# FEU_Last.net
KiCad netlist of a schematic drawn in EAGLE
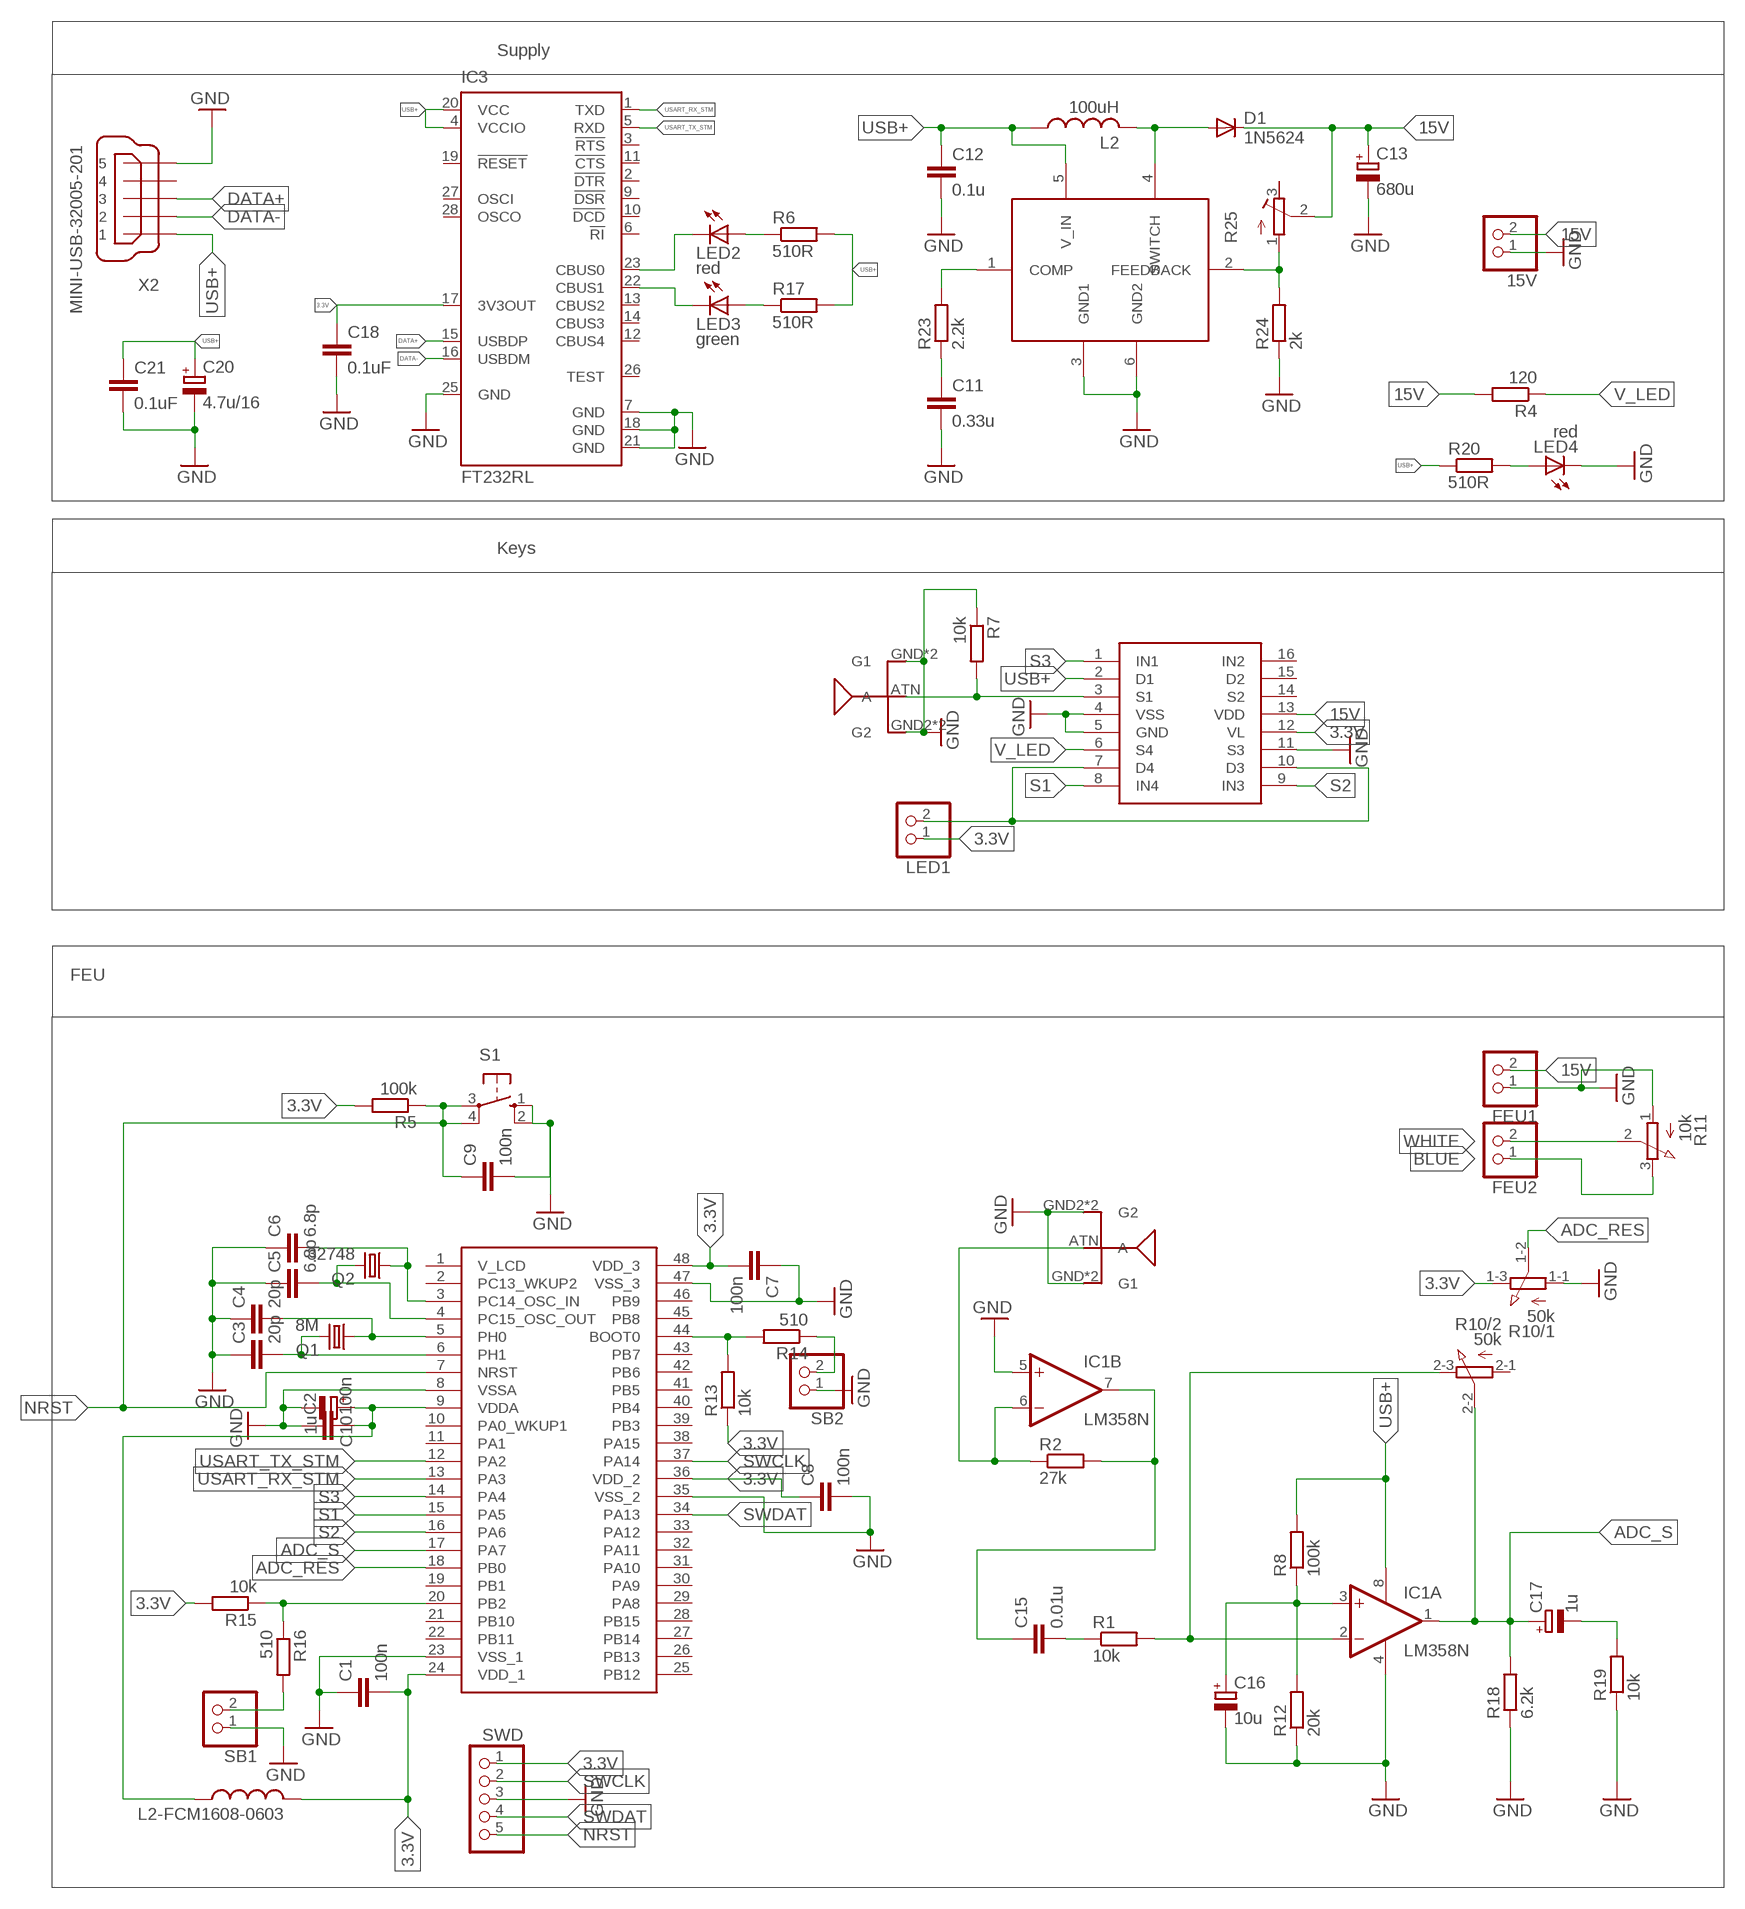
[diagram p0: schematic, sheet 1]

(export (version "E")
  (design (tool "Eeschema 10.0.6"))
  (components
    (comp (ref "15V")
      (value "PINHD-1X2")
      (footprint "eagle-import:1X02")
      (libsource (lib "eagle-import") (part "PINHD-1X2"))
    )
    (comp (ref "C1")
      (value "100n")
      (footprint "eagle-import:C0805")
      (libsource (lib "eagle-import") (part "C-EUC0805"))
    )
    (comp (ref "C2")
      (value "100n")
      (footprint "eagle-import:C0805")
      (libsource (lib "eagle-import") (part "C-EUC0805"))
    )
    (comp (ref "C3")
      (value "20p")
      (footprint "eagle-import:C0805")
      (libsource (lib "eagle-import") (part "C-EUC0805"))
    )
    (comp (ref "C4")
      (value "20p")
      (footprint "eagle-import:C0805")
      (libsource (lib "eagle-import") (part "C-EUC0805"))
    )
    (comp (ref "C5")
      (value "6.8p")
      (footprint "eagle-import:C0805")
      (libsource (lib "eagle-import") (part "C-EUC0805"))
    )
    (comp (ref "C6")
      (value "6.8p")
      (footprint "eagle-import:C0805")
      (libsource (lib "eagle-import") (part "C-EUC0805"))
    )
    (comp (ref "C7")
      (value "100n")
      (footprint "eagle-import:C0805")
      (libsource (lib "eagle-import") (part "C-EUC0805"))
    )
    (comp (ref "C8")
      (value "100n")
      (footprint "eagle-import:C0805")
      (libsource (lib "eagle-import") (part "C-EUC0805"))
    )
    (comp (ref "C9")
      (value "100n")
      (footprint "eagle-import:C0805")
      (libsource (lib "eagle-import") (part "C-EUC0805"))
    )
    (comp (ref "C10")
      (value "1u")
      (footprint "eagle-import:A_3216-18W")
      (libsource (lib "eagle-import") (part "CPOL-EUA/3216-18W"))
    )
    (comp (ref "C11")
      (value "0.33u")
      (footprint "eagle-import:C0805")
      (libsource (lib "eagle-import") (part "C-EUC0805"))
    )
    (comp (ref "C12")
      (value "0.1u")
      (footprint "eagle-import:C0805")
      (libsource (lib "eagle-import") (part "C-EUC0805"))
    )
    (comp (ref "C13")
      (value "680u")
      (footprint "eagle-import:E5-5")
      (libsource (lib "eagle-import") (part "CPOL-EUE5-5"))
    )
    (comp (ref "C15")
      (value "0.01u")
      (footprint "eagle-import:C0805")
      (libsource (lib "eagle-import") (part "C-EUC0805"))
    )
    (comp (ref "C16")
      (value "10u")
      (footprint "eagle-import:E3,5-8")
      (libsource (lib "eagle-import") (part "CPOL-EUE3.5-8"))
    )
    (comp (ref "C17")
      (value "1u")
      (footprint "eagle-import:E3,5-8")
      (libsource (lib "eagle-import") (part "CPOL-EUE3.5-8"))
    )
    (comp (ref "C18")
      (value "0.1uF")
      (footprint "eagle-import:C0805")
      (libsource (lib "eagle-import") (part "C-EUC0805"))
    )
    (comp (ref "C20")
      (value "4.7u/16")
      (footprint "eagle-import:E2-5")
      (libsource (lib "eagle-import") (part "CPOL-EUE2-5"))
    )
    (comp (ref "C21")
      (value "0.1uF")
      (footprint "eagle-import:C0805")
      (libsource (lib "eagle-import") (part "C-EUC0805"))
    )
    (comp (ref "D1")
      (value "1N5624")
      (footprint "eagle-import:DO201-15")
      (libsource (lib "eagle-import") (part "1N5624"))
    )
    (comp (ref "FEU1")
      (value "PINHD-1X2")
      (footprint "eagle-import:1X02")
      (libsource (lib "eagle-import") (part "PINHD-1X2"))
    )
    (comp (ref "FEU2")
      (value "PINHD-1X2")
      (footprint "eagle-import:1X02")
      (libsource (lib "eagle-import") (part "PINHD-1X2"))
    )
    (comp (ref "IC1")
      (value "LM358N")
      (footprint "eagle-import:DIL08")
      (libsource (lib "eagle-import") (part "LM358N"))
    )
    (comp (ref "IC3")
      (value "FT232RL")
      (footprint "eagle-import:SSOP28")
      (libsource (lib "eagle-import") (part "FT232RL"))
    )
    (comp (ref "L2")
      (value "100uH")
      (footprint "eagle-import:0207_5V")
      (libsource (lib "eagle-import") (part "L-US0207/5V"))
    )
    (comp (ref "L2-FCM1608-0603")
      (value "L-USL3216C")
      (footprint "eagle-import:L3216C")
      (libsource (lib "eagle-import") (part "L-USL3216C"))
    )
    (comp (ref "LED1")
      (value "PINHD-1X2")
      (footprint "eagle-import:1X02")
      (libsource (lib "eagle-import") (part "PINHD-1X2"))
    )
    (comp (ref "LED2")
      (value "red")
      (footprint "eagle-import:CHIPLED_1206")
      (libsource (lib "eagle-import") (part "LEDCHIPLED_1206"))
    )
    (comp (ref "LED3")
      (value "green")
      (footprint "eagle-import:CHIPLED_1206")
      (libsource (lib "eagle-import") (part "LEDCHIPLED_1206"))
    )
    (comp (ref "LED4")
      (value "red")
      (footprint "eagle-import:CHIPLED_1206")
      (libsource (lib "eagle-import") (part "LEDCHIPLED_1206"))
    )
    (comp (ref "Q1")
      (value "8M")
      (footprint "eagle-import:HC49_S")
      (fields (field (name "OC_FARNELL") "1667008"))
      (libsource (lib "eagle-import") (part "CRYSTALHC49S"))
    )
    (comp (ref "Q2")
      (value "32748")
      (footprint "eagle-import:TC26H")
      (libsource (lib "eagle-import") (part "CRYSTALTC26H"))
    )
    (comp (ref "R1")
      (value "10k")
      (footprint "eagle-import:R0805")
      (libsource (lib "eagle-import") (part "R-EU_R0805"))
    )
    (comp (ref "R2")
      (value "27k")
      (footprint "eagle-import:R0805")
      (libsource (lib "eagle-import") (part "R-EU_R0805"))
    )
    (comp (ref "R4")
      (value "120")
      (footprint "eagle-import:R0805")
      (libsource (lib "eagle-import") (part "R-EU_R0805"))
    )
    (comp (ref "R5")
      (value "100k")
      (footprint "eagle-import:R0805")
      (libsource (lib "eagle-import") (part "R-EU_R0805"))
    )
    (comp (ref "R6")
      (value "510R")
      (footprint "eagle-import:R0805W")
      (libsource (lib "eagle-import") (part "R-EU_R0805W"))
    )
    (comp (ref "R7")
      (value "10k")
      (footprint "eagle-import:R0805")
      (libsource (lib "eagle-import") (part "R-EU_R0805"))
    )
    (comp (ref "R8")
      (value "100k")
      (footprint "eagle-import:R0805")
      (libsource (lib "eagle-import") (part "R-EU_R0805"))
    )
    (comp (ref "R10")
      (value "50k")
      (footprint "eagle-import:3RP_1610G")
      (libsource (lib "eagle-import") (part "3RP/1610G"))
    )
    (comp (ref "R11")
      (value "10k")
      (footprint "eagle-import:3RP_1610N")
      (libsource (lib "eagle-import") (part "3RP/1610N"))
    )
    (comp (ref "R12")
      (value "20k")
      (footprint "eagle-import:R0805")
      (libsource (lib "eagle-import") (part "R-EU_R0805"))
    )
    (comp (ref "R13")
      (value "10k")
      (footprint "eagle-import:R0805")
      (libsource (lib "eagle-import") (part "R-EU_R0805"))
    )
    (comp (ref "R14")
      (value "510")
      (footprint "eagle-import:R0805")
      (libsource (lib "eagle-import") (part "R-EU_R0805"))
    )
    (comp (ref "R15")
      (value "10k")
      (footprint "eagle-import:M0805")
      (libsource (lib "eagle-import") (part "R-EU_M0805"))
    )
    (comp (ref "R16")
      (value "510")
      (footprint "eagle-import:R0805")
      (libsource (lib "eagle-import") (part "R-EU_R0805"))
    )
    (comp (ref "R17")
      (value "510R")
      (footprint "eagle-import:R0805W")
      (libsource (lib "eagle-import") (part "R-EU_R0805W"))
    )
    (comp (ref "R18")
      (value "6.2k")
      (footprint "eagle-import:R0805")
      (libsource (lib "eagle-import") (part "R-EU_R0805"))
    )
    (comp (ref "R19")
      (value "10k")
      (footprint "eagle-import:R0805")
      (libsource (lib "eagle-import") (part "R-EU_R0805"))
    )
    (comp (ref "R20")
      (value "510R")
      (footprint "eagle-import:R0805W")
      (libsource (lib "eagle-import") (part "R-EU_R0805W"))
    )
    (comp (ref "R23")
      (value "2.2k")
      (footprint "eagle-import:R0805")
      (libsource (lib "eagle-import") (part "R-EU_R0805"))
    )
    (comp (ref "R24")
      (value "2k")
      (footprint "eagle-import:R0805")
      (libsource (lib "eagle-import") (part "R-EU_R0805"))
    )
    (comp (ref "R25")
      (value "R-TRIMM3339P")
      (footprint "eagle-import:RTRIM3339P")
      (libsource (lib "eagle-import") (part "R-TRIMM3339P"))
    )
    (comp (ref "S1")
      (value "10-XX")
      (footprint "eagle-import:B3F-10XX")
      (fields (field (name "MPN") "B3F-1000"))
      (libsource (lib "eagle-import") (part "10-XX"))
    )
    (comp (ref "SB1")
      (value "PINHD-1X2")
      (footprint "eagle-import:1X02")
      (libsource (lib "eagle-import") (part "PINHD-1X2"))
    )
    (comp (ref "SB2")
      (value "PINHD-1X2")
      (footprint "eagle-import:1X02")
      (libsource (lib "eagle-import") (part "PINHD-1X2"))
    )
    (comp (ref "SWD")
      (value "PINHD-1X5")
      (footprint "eagle-import:1X05")
      (libsource (lib "eagle-import") (part "PINHD-1X5"))
    )
    (comp (ref "U$1")
      (value "STM32L152C6")
      (footprint "eagle-import:LQFP48")
      (libsource (lib "eagle-import") (part "STM32L152C6"))
    )
    (comp (ref "U$2")
      (value "GSM_ANT")
      (footprint "eagle-import:GSM")
      (libsource (lib "eagle-import") (part "GSM_ANT"))
    )
    (comp (ref "U$3")
      (value "GSM_ANT")
      (footprint "eagle-import:GSM")
      (libsource (lib "eagle-import") (part "GSM_ANT"))
    )
    (comp (ref "U$4")
      (value "LM2577")
      (footprint "eagle-import:TO263-5")
      (libsource (lib "eagle-import") (part "LM2577"))
    )
    (comp (ref "U$5")
      (value "ADG433BN")
      (footprint "eagle-import:DIL16")
      (libsource (lib "eagle-import") (part "ADG433BN"))
    )
    (comp (ref "X2")
      (value "MINI-USB-32005-201")
      (footprint "eagle-import:32005-201")
      (libsource (lib "eagle-import") (part "MINI-USB-32005-201"))
    )
  )
  (nets
    (net (code "1") (name "3.3V") (class "Default")
      (node (ref "C1") (pin "2") (pinfunction "2_2") (pintype "passive"))
      (node (ref "C18") (pin "1") (pinfunction "1_1") (pintype "passive"))
      (node (ref "C7") (pin "2") (pinfunction "2_2") (pintype "passive"))
      (node (ref "C8") (pin "1") (pinfunction "1_1") (pintype "passive"))
      (node (ref "IC3") (pin "17") (pinfunction "3V3OUT_17") (pintype "output"))
      (node (ref "L2-FCM1608-0603") (pin "2") (pinfunction "2_2") (pintype "passive"))
      (node (ref "LED1") (pin "1") (pinfunction "1_1") (pintype "passive"))
      (node (ref "R10") (pin "1-3") (pinfunction "E_1-3") (pintype "passive"))
      (node (ref "R13") (pin "1") (pinfunction "1_1") (pintype "passive"))
      (node (ref "R15") (pin "2") (pinfunction "2_2") (pintype "passive"))
      (node (ref "R5") (pin "2") (pinfunction "2_2") (pintype "passive"))
      (node (ref "SWD") (pin "1") (pinfunction "1_1") (pintype "passive"))
      (node (ref "U$1") (pin "24") (pinfunction "VDD_1_24") (pintype "bidirectional"))
      (node (ref "U$1") (pin "36") (pinfunction "VDD_2_36") (pintype "bidirectional"))
      (node (ref "U$1") (pin "48") (pinfunction "VDD_3_48") (pintype "bidirectional"))
      (node (ref "U$5") (pin "12") (pinfunction "VL_12") (pintype "bidirectional"))
    )
    (net (code "2") (name "15V") (class "Default")
      (node (ref "15V") (pin "2") (pinfunction "2_2") (pintype "passive"))
      (node (ref "C13") (pin "+") (pinfunction "+_+") (pintype "passive"))
      (node (ref "D1") (pin "C") (pinfunction "C_C") (pintype "passive"))
      (node (ref "FEU1") (pin "2") (pinfunction "2_2") (pintype "passive"))
      (node (ref "R25") (pin "2") (pinfunction "S_2") (pintype "passive"))
      (node (ref "R4") (pin "2") (pinfunction "2_2") (pintype "passive"))
      (node (ref "U$5") (pin "13") (pinfunction "VDD_13") (pintype "bidirectional"))
    )
    (net (code "3") (name "ADC_RES") (class "Default")
      (node (ref "R10") (pin "1-2") (pinfunction "S_1-2") (pintype "passive"))
      (node (ref "U$1") (pin "18") (pinfunction "PB0_18") (pintype "bidirectional"))
    )
    (net (code "4") (name "ADC_S") (class "Default")
      (node (ref "C17") (pin "+") (pinfunction "+_+") (pintype "passive"))
      (node (ref "IC1") (pin "1") (pinfunction "OUT_1") (pintype "output"))
      (node (ref "R10") (pin "2-2") (pinfunction "S_2-2") (pintype "passive"))
      (node (ref "R18") (pin "2") (pinfunction "2_2") (pintype "passive"))
      (node (ref "U$1") (pin "17") (pinfunction "PA7_17") (pintype "bidirectional"))
    )
    (net (code "5") (name "BLUE") (class "Default")
      (node (ref "FEU2") (pin "1") (pinfunction "1_1") (pintype "passive"))
      (node (ref "R11") (pin "3") (pinfunction "E_3") (pintype "passive"))
    )
    (net (code "6") (name "DATA+") (class "Default")
      (node (ref "IC3") (pin "15") (pinfunction "USBDP_15") (pintype "bidirectional"))
      (node (ref "X2") (pin "3") (pinfunction "3_3") (pintype "passive"))
    )
    (net (code "7") (name "DATA-") (class "Default")
      (node (ref "IC3") (pin "16") (pinfunction "USBDM_16") (pintype "bidirectional"))
      (node (ref "X2") (pin "2") (pinfunction "2_2") (pintype "passive"))
    )
    (net (code "8") (name "GND") (class "Default")
      (node (ref "15V") (pin "1") (pinfunction "1_1") (pintype "passive"))
      (node (ref "C1") (pin "1") (pinfunction "1_1") (pintype "passive"))
      (node (ref "C10") (pin "-") (pinfunction "-_-") (pintype "passive"))
      (node (ref "C11") (pin "2") (pinfunction "2_2") (pintype "passive"))
      (node (ref "C12") (pin "2") (pinfunction "2_2") (pintype "passive"))
      (node (ref "C13") (pin "-") (pinfunction "-_-") (pintype "passive"))
      (node (ref "C16") (pin "-") (pinfunction "-_-") (pintype "passive"))
      (node (ref "C18") (pin "2") (pinfunction "2_2") (pintype "passive"))
      (node (ref "C2") (pin "1") (pinfunction "1_1") (pintype "passive"))
      (node (ref "C20") (pin "-") (pinfunction "-_-") (pintype "passive"))
      (node (ref "C21") (pin "2") (pinfunction "2_2") (pintype "passive"))
      (node (ref "C3") (pin "1") (pinfunction "1_1") (pintype "passive"))
      (node (ref "C4") (pin "1") (pinfunction "1_1") (pintype "passive"))
      (node (ref "C5") (pin "1") (pinfunction "1_1") (pintype "passive"))
      (node (ref "C6") (pin "1") (pinfunction "1_1") (pintype "passive"))
      (node (ref "C7") (pin "1") (pinfunction "1_1") (pintype "passive"))
      (node (ref "C8") (pin "2") (pinfunction "2_2") (pintype "passive"))
      (node (ref "C9") (pin "2") (pinfunction "2_2") (pintype "passive"))
      (node (ref "FEU1") (pin "1") (pinfunction "1_1") (pintype "passive"))
      (node (ref "IC1") (pin "4") (pinfunction "V-_4") (pintype "power_in"))
      (node (ref "IC1") (pin "5") (pinfunction "+IN_5") (pintype "input"))
      (node (ref "IC3") (pin "18") (pinfunction "GND_18") (pintype "power_in"))
      (node (ref "IC3") (pin "21") (pinfunction "GND_21") (pintype "power_in"))
      (node (ref "IC3") (pin "25") (pinfunction "GND_25") (pintype "power_in"))
      (node (ref "IC3") (pin "7") (pinfunction "GND_7") (pintype "power_in"))
      (node (ref "LED4") (pin "C") (pinfunction "C_C") (pintype "passive"))
      (node (ref "R10") (pin "1-1") (pinfunction "A_1-1") (pintype "passive"))
      (node (ref "R11") (pin "1") (pinfunction "A_1") (pintype "passive"))
      (node (ref "R12") (pin "1") (pinfunction "1_1") (pintype "passive"))
      (node (ref "R18") (pin "1") (pinfunction "1_1") (pintype "passive"))
      (node (ref "R19") (pin "1") (pinfunction "1_1") (pintype "passive"))
      (node (ref "R24") (pin "1") (pinfunction "1_1") (pintype "passive"))
      (node (ref "R7") (pin "1") (pinfunction "1_1") (pintype "passive"))
      (node (ref "S1") (pin "1") (pinfunction "S_1") (pintype "passive"))
      (node (ref "S1") (pin "2") (pinfunction "S1_2") (pintype "passive"))
      (node (ref "SB1") (pin "1") (pinfunction "1_1") (pintype "passive"))
      (node (ref "SB2") (pin "1") (pinfunction "1_1") (pintype "passive"))
      (node (ref "SWD") (pin "3") (pinfunction "3_3") (pintype "passive"))
      (node (ref "U$1") (pin "23") (pinfunction "VSS_1_23") (pintype "bidirectional"))
      (node (ref "U$1") (pin "35") (pinfunction "VSS_2_35") (pintype "bidirectional"))
      (node (ref "U$1") (pin "47") (pinfunction "VSS_3_47") (pintype "bidirectional"))
      (node (ref "U$1") (pin "8") (pinfunction "VSSA_8") (pintype "bidirectional"))
      (node (ref "U$2") (pin "GND") (pinfunction "G1_GND") (pintype "bidirectional"))
      (node (ref "U$2") (pin "GND1") (pinfunction "G1_GND1") (pintype "bidirectional"))
      (node (ref "U$2") (pin "GND2") (pinfunction "G2_GND2") (pintype "bidirectional"))
      (node (ref "U$2") (pin "GND3") (pinfunction "G2_GND3") (pintype "bidirectional"))
      (node (ref "U$3") (pin "GND") (pinfunction "G1_GND") (pintype "bidirectional"))
      (node (ref "U$3") (pin "GND1") (pinfunction "G1_GND1") (pintype "bidirectional"))
      (node (ref "U$3") (pin "GND2") (pinfunction "G2_GND2") (pintype "bidirectional"))
      (node (ref "U$3") (pin "GND3") (pinfunction "G2_GND3") (pintype "bidirectional"))
      (node (ref "U$4") (pin "3") (pinfunction "GND1_3") (pintype "bidirectional"))
      (node (ref "U$4") (pin "6") (pinfunction "GND2_6") (pintype "bidirectional"))
      (node (ref "U$5") (pin "11") (pinfunction "S3_11") (pintype "bidirectional"))
      (node (ref "U$5") (pin "4") (pinfunction "VSS_4") (pintype "bidirectional"))
      (node (ref "U$5") (pin "5") (pinfunction "GND_5") (pintype "bidirectional"))
      (node (ref "X2") (pin "5") (pinfunction "5_5") (pintype "passive"))
    )
    (net (code "9") (name "NRST") (class "Default")
      (node (ref "C9") (pin "1") (pinfunction "1_1") (pintype "passive"))
      (node (ref "R5") (pin "1") (pinfunction "1_1") (pintype "passive"))
      (node (ref "S1") (pin "3") (pinfunction "P_3") (pintype "passive"))
      (node (ref "S1") (pin "4") (pinfunction "P1_4") (pintype "passive"))
      (node (ref "SWD") (pin "5") (pinfunction "5_5") (pintype "passive"))
      (node (ref "U$1") (pin "7") (pinfunction "NRST_7") (pintype "bidirectional"))
    )
    (net (code "10") (name "Net-(C11-Pad1)") (class "Default")
      (node (ref "C11") (pin "1") (pinfunction "1_1") (pintype "passive"))
      (node (ref "R23") (pin "1") (pinfunction "1_1") (pintype "passive"))
    )
    (net (code "11") (name "Net-(C15-Pad2)") (class "Default")
      (node (ref "C15") (pin "2") (pinfunction "2_2") (pintype "passive"))
      (node (ref "R1") (pin "1") (pinfunction "1_1") (pintype "passive"))
    )
    (net (code "12") (name "Net-(C17-Pad-)") (class "Default")
      (node (ref "C17") (pin "-") (pinfunction "-_-") (pintype "passive"))
      (node (ref "R19") (pin "2") (pinfunction "2_2") (pintype "passive"))
    )
    (net (code "13") (name "Net-(IC1A-+IN)") (class "Default")
      (node (ref "C16") (pin "+") (pinfunction "+_+") (pintype "passive"))
      (node (ref "IC1") (pin "3") (pinfunction "+IN_3") (pintype "input"))
      (node (ref "R12") (pin "2") (pinfunction "2_2") (pintype "passive"))
      (node (ref "R8") (pin "1") (pinfunction "1_1") (pintype "passive"))
    )
    (net (code "14") (name "Net-(IC1A--IN)") (class "Default")
      (node (ref "IC1") (pin "2") (pinfunction "-IN_2") (pintype "input"))
      (node (ref "R1") (pin "2") (pinfunction "2_2") (pintype "passive"))
      (node (ref "R10") (pin "2-3") (pinfunction "E_2-3") (pintype "passive"))
    )
    (net (code "15") (name "Net-(IC1B--IN)") (class "Default")
      (node (ref "IC1") (pin "6") (pinfunction "-IN_6") (pintype "input"))
      (node (ref "R2") (pin "1") (pinfunction "1_1") (pintype "passive"))
      (node (ref "U$2") (pin "ATN") (pinfunction "A_ATN") (pintype "bidirectional"))
    )
    (net (code "16") (name "Net-(IC1B-OUT)") (class "Default")
      (node (ref "C15") (pin "1") (pinfunction "1_1") (pintype "passive"))
      (node (ref "IC1") (pin "7") (pinfunction "OUT_7") (pintype "output"))
      (node (ref "R2") (pin "2") (pinfunction "2_2") (pintype "passive"))
    )
    (net (code "17") (name "Net-(IC3-CBUS0)") (class "Default")
      (node (ref "IC3") (pin "23") (pinfunction "CBUS0_23") (pintype "bidirectional"))
      (node (ref "LED2") (pin "C") (pinfunction "C_C") (pintype "passive"))
    )
    (net (code "18") (name "Net-(IC3-CBUS1)") (class "Default")
      (node (ref "IC3") (pin "22") (pinfunction "CBUS1_22") (pintype "bidirectional"))
      (node (ref "LED3") (pin "C") (pinfunction "C_C") (pintype "passive"))
    )
    (net (code "19") (name "Net-(LED2-PadA)") (class "Default")
      (node (ref "LED2") (pin "A") (pinfunction "A_A") (pintype "passive"))
      (node (ref "R6") (pin "1") (pinfunction "1_1") (pintype "passive"))
    )
    (net (code "20") (name "Net-(LED3-PadA)") (class "Default")
      (node (ref "LED3") (pin "A") (pinfunction "A_A") (pintype "passive"))
      (node (ref "R17") (pin "1") (pinfunction "1_1") (pintype "passive"))
    )
    (net (code "21") (name "Net-(LED4-PadA)") (class "Default")
      (node (ref "LED4") (pin "A") (pinfunction "A_A") (pintype "passive"))
      (node (ref "R20") (pin "2") (pinfunction "2_2") (pintype "passive"))
    )
    (net (code "22") (name "Net-(R14-Pad1)") (class "Default")
      (node (ref "R14") (pin "1") (pinfunction "1_1") (pintype "passive"))
      (node (ref "SB2") (pin "2") (pinfunction "2_2") (pintype "passive"))
    )
    (net (code "23") (name "Net-(R16-Pad2)") (class "Default")
      (node (ref "R16") (pin "2") (pinfunction "2_2") (pintype "passive"))
      (node (ref "SB1") (pin "2") (pinfunction "2_2") (pintype "passive"))
    )
    (net (code "24") (name "Net-(R25-E)") (class "Default")
      (node (ref "R24") (pin "2") (pinfunction "2_2") (pintype "passive"))
      (node (ref "R25") (pin "1") (pinfunction "E_1") (pintype "passive"))
      (node (ref "U$4") (pin "2") (pinfunction "FEEDBACK_2") (pintype "bidirectional"))
    )
    (net (code "25") (name "Net-(U$1-BOOT0)") (class "Default")
      (node (ref "R13") (pin "2") (pinfunction "2_2") (pintype "passive"))
      (node (ref "R14") (pin "2") (pinfunction "2_2") (pintype "passive"))
      (node (ref "U$1") (pin "44") (pinfunction "BOOT0_44") (pintype "bidirectional"))
    )
    (net (code "26") (name "Net-(U$1-PB2)") (class "Default")
      (node (ref "R15") (pin "1") (pinfunction "1_1") (pintype "passive"))
      (node (ref "R16") (pin "1") (pinfunction "1_1") (pintype "passive"))
      (node (ref "U$1") (pin "20") (pinfunction "PB2_20") (pintype "bidirectional"))
    )
    (net (code "27") (name "Net-(U$1-PC14_OSC_IN)") (class "Default")
      (node (ref "C6") (pin "2") (pinfunction "2_2") (pintype "passive"))
      (node (ref "Q2") (pin "1") (pinfunction "1_1") (pintype "passive"))
      (node (ref "U$1") (pin "3") (pinfunction "PC14_OSC_IN_3") (pintype "bidirectional"))
    )
    (net (code "28") (name "Net-(U$1-PC15_OSC_OUT)") (class "Default")
      (node (ref "C5") (pin "2") (pinfunction "2_2") (pintype "passive"))
      (node (ref "Q2") (pin "2") (pinfunction "2_2") (pintype "passive"))
      (node (ref "U$1") (pin "4") (pinfunction "PC15_OSC_OUT_4") (pintype "bidirectional"))
    )
    (net (code "29") (name "Net-(U$1-PH0)") (class "Default")
      (node (ref "C4") (pin "2") (pinfunction "2_2") (pintype "passive"))
      (node (ref "Q1") (pin "1") (pinfunction "1_1") (pintype "passive"))
      (node (ref "U$1") (pin "5") (pinfunction "PH0_5") (pintype "bidirectional"))
    )
    (net (code "30") (name "Net-(U$1-PH1)") (class "Default")
      (node (ref "C3") (pin "2") (pinfunction "2_2") (pintype "passive"))
      (node (ref "Q1") (pin "2") (pinfunction "2_2") (pintype "passive"))
      (node (ref "U$1") (pin "6") (pinfunction "PH1_6") (pintype "bidirectional"))
    )
    (net (code "31") (name "Net-(U$1-VDDA)") (class "Default")
      (node (ref "C10") (pin "+") (pinfunction "+_+") (pintype "passive"))
      (node (ref "C2") (pin "2") (pinfunction "2_2") (pintype "passive"))
      (node (ref "L2-FCM1608-0603") (pin "1") (pinfunction "1_1") (pintype "passive"))
      (node (ref "U$1") (pin "9") (pinfunction "VDDA_9") (pintype "bidirectional"))
    )
    (net (code "32") (name "Net-(U$3-A)") (class "Default")
      (node (ref "R7") (pin "2") (pinfunction "2_2") (pintype "passive"))
      (node (ref "U$3") (pin "ATN") (pinfunction "A_ATN") (pintype "bidirectional"))
      (node (ref "U$5") (pin "3") (pinfunction "S1_3") (pintype "bidirectional"))
    )
    (net (code "33") (name "Net-(U$4-COMP)") (class "Default")
      (node (ref "R23") (pin "2") (pinfunction "2_2") (pintype "passive"))
      (node (ref "U$4") (pin "1") (pinfunction "COMP_1") (pintype "bidirectional"))
    )
    (net (code "34") (name "Net-(U$4-SWITCH)") (class "Default")
      (node (ref "D1") (pin "A") (pinfunction "A_A") (pintype "passive"))
      (node (ref "L2") (pin "2") (pinfunction "2_2") (pintype "passive"))
      (node (ref "U$4") (pin "4") (pinfunction "SWITCH_4") (pintype "bidirectional"))
    )
    (net (code "35") (name "Net-(U$5-D3)") (class "Default")
      (node (ref "LED1") (pin "2") (pinfunction "2_2") (pintype "passive"))
      (node (ref "U$5") (pin "10") (pinfunction "D3_10") (pintype "bidirectional"))
      (node (ref "U$5") (pin "7") (pinfunction "D4_7") (pintype "bidirectional"))
    )
    (net (code "36") (name "S1") (class "Default")
      (node (ref "U$1") (pin "15") (pinfunction "PA5_15") (pintype "bidirectional"))
      (node (ref "U$5") (pin "8") (pinfunction "IN4_8") (pintype "bidirectional"))
    )
    (net (code "37") (name "S2") (class "Default")
      (node (ref "U$1") (pin "16") (pinfunction "PA6_16") (pintype "bidirectional"))
      (node (ref "U$5") (pin "9") (pinfunction "IN3_9") (pintype "bidirectional"))
    )
    (net (code "38") (name "S3") (class "Default")
      (node (ref "U$1") (pin "14") (pinfunction "PA4_14") (pintype "bidirectional"))
      (node (ref "U$5") (pin "1") (pinfunction "IN1_1") (pintype "bidirectional"))
    )
    (net (code "39") (name "SWCLK") (class "Default")
      (node (ref "SWD") (pin "2") (pinfunction "2_2") (pintype "passive"))
      (node (ref "U$1") (pin "37") (pinfunction "PA14_37") (pintype "bidirectional"))
    )
    (net (code "40") (name "SWDAT") (class "Default")
      (node (ref "SWD") (pin "4") (pinfunction "4_4") (pintype "passive"))
      (node (ref "U$1") (pin "34") (pinfunction "PA13_34") (pintype "bidirectional"))
    )
    (net (code "41") (name "USART_RX_STM") (class "Default")
      (node (ref "IC3") (pin "1") (pinfunction "TXD_1") (pintype "output"))
      (node (ref "U$1") (pin "13") (pinfunction "PA3_13") (pintype "bidirectional"))
    )
    (net (code "42") (name "USART_TX_STM") (class "Default")
      (node (ref "IC3") (pin "5") (pinfunction "RXD_5") (pintype "input"))
      (node (ref "U$1") (pin "12") (pinfunction "PA2_12") (pintype "bidirectional"))
    )
    (net (code "43") (name "USB+") (class "Default")
      (node (ref "C12") (pin "1") (pinfunction "1_1") (pintype "passive"))
      (node (ref "C20") (pin "+") (pinfunction "+_+") (pintype "passive"))
      (node (ref "C21") (pin "1") (pinfunction "1_1") (pintype "passive"))
      (node (ref "IC1") (pin "8") (pinfunction "V+_8") (pintype "power_in"))
      (node (ref "IC3") (pin "20") (pinfunction "VCC_20") (pintype "power_in"))
      (node (ref "IC3") (pin "4") (pinfunction "VCCIO_4") (pintype "power_in"))
      (node (ref "L2") (pin "1") (pinfunction "1_1") (pintype "passive"))
      (node (ref "R17") (pin "2") (pinfunction "2_2") (pintype "passive"))
      (node (ref "R20") (pin "1") (pinfunction "1_1") (pintype "passive"))
      (node (ref "R6") (pin "2") (pinfunction "2_2") (pintype "passive"))
      (node (ref "R8") (pin "2") (pinfunction "2_2") (pintype "passive"))
      (node (ref "U$4") (pin "5") (pinfunction "V_IN_5") (pintype "bidirectional"))
      (node (ref "U$5") (pin "2") (pinfunction "D1_2") (pintype "bidirectional"))
      (node (ref "X2") (pin "1") (pinfunction "1_1") (pintype "passive"))
    )
    (net (code "44") (name "V_LED") (class "Default")
      (node (ref "R4") (pin "1") (pinfunction "1_1") (pintype "passive"))
      (node (ref "U$5") (pin "6") (pinfunction "S4_6") (pintype "bidirectional"))
    )
    (net (code "45") (name "WHITE") (class "Default")
      (node (ref "FEU2") (pin "2") (pinfunction "2_2") (pintype "passive"))
      (node (ref "R11") (pin "2") (pinfunction "S_2") (pintype "passive"))
    )
    (net (code "46") (name "unconnected-(IC3-CBUS2-Pad13)") (class "Default")
      (node (ref "IC3") (pin "13") (pinfunction "CBUS2_13") (pintype "bidirectional"))
    )
    (net (code "47") (name "unconnected-(IC3-CBUS3-Pad14)") (class "Default")
      (node (ref "IC3") (pin "14") (pinfunction "CBUS3_14") (pintype "bidirectional"))
    )
    (net (code "48") (name "unconnected-(IC3-CBUS4-Pad12)") (class "Default")
      (node (ref "IC3") (pin "12") (pinfunction "CBUS4_12") (pintype "bidirectional"))
    )
    (net (code "49") (name "unconnected-(IC3-OSCI-Pad27)") (class "Default")
      (node (ref "IC3") (pin "27") (pinfunction "OSCI_27") (pintype "input"))
    )
    (net (code "50") (name "unconnected-(IC3-OSCO-Pad28)") (class "Default")
      (node (ref "IC3") (pin "28") (pinfunction "OSCO_28") (pintype "output"))
    )
    (net (code "51") (name "unconnected-(IC3-TEST-Pad26)") (class "Default")
      (node (ref "IC3") (pin "26") (pinfunction "TEST_26") (pintype "input"))
    )
    (net (code "52") (name "unconnected-(IC3-~{CTS}-Pad11)") (class "Default")
      (node (ref "IC3") (pin "11") (pinfunction "~{CTS}_11") (pintype "input"))
    )
    (net (code "53") (name "unconnected-(IC3-~{DCD}-Pad10)") (class "Default")
      (node (ref "IC3") (pin "10") (pinfunction "~{DCD}_10") (pintype "input"))
    )
    (net (code "54") (name "unconnected-(IC3-~{DSR}-Pad9)") (class "Default")
      (node (ref "IC3") (pin "9") (pinfunction "~{DSR}_9") (pintype "input"))
    )
    (net (code "55") (name "unconnected-(IC3-~{DTR}-Pad2)") (class "Default")
      (node (ref "IC3") (pin "2") (pinfunction "~{DTR}_2") (pintype "output"))
    )
    (net (code "56") (name "unconnected-(IC3-~{RESET}-Pad19)") (class "Default")
      (node (ref "IC3") (pin "19") (pinfunction "~{RESET}_19") (pintype "input"))
    )
    (net (code "57") (name "unconnected-(IC3-~{RI}-Pad6)") (class "Default")
      (node (ref "IC3") (pin "6") (pinfunction "~{RI}_6") (pintype "input"))
    )
    (net (code "58") (name "unconnected-(IC3-~{RTS}-Pad3)") (class "Default")
      (node (ref "IC3") (pin "3") (pinfunction "~{RTS}_3") (pintype "output"))
    )
    (net (code "59") (name "unconnected-(R10B-A-Pad2-1)") (class "Default")
      (node (ref "R10") (pin "2-1") (pinfunction "A_2-1") (pintype "passive"))
    )
    (net (code "60") (name "unconnected-(R25-A-Pad3)") (class "Default")
      (node (ref "R25") (pin "3") (pinfunction "A_3") (pintype "passive"))
    )
    (net (code "61") (name "unconnected-(U$1-PA0_WKUP1-Pad10)") (class "Default")
      (node (ref "U$1") (pin "10") (pinfunction "PA0_WKUP1_10") (pintype "bidirectional"))
    )
    (net (code "62") (name "unconnected-(U$1-PA1-Pad11)") (class "Default")
      (node (ref "U$1") (pin "11") (pinfunction "PA1_11") (pintype "bidirectional"))
    )
    (net (code "63") (name "unconnected-(U$1-PA8-Pad29)") (class "Default")
      (node (ref "U$1") (pin "29") (pinfunction "PA8_29") (pintype "bidirectional"))
    )
    (net (code "64") (name "unconnected-(U$1-PA9-Pad30)") (class "Default")
      (node (ref "U$1") (pin "30") (pinfunction "PA9_30") (pintype "bidirectional"))
    )
    (net (code "65") (name "unconnected-(U$1-PA10-Pad31)") (class "Default")
      (node (ref "U$1") (pin "31") (pinfunction "PA10_31") (pintype "bidirectional"))
    )
    (net (code "66") (name "unconnected-(U$1-PA11-Pad32)") (class "Default")
      (node (ref "U$1") (pin "32") (pinfunction "PA11_32") (pintype "bidirectional"))
    )
    (net (code "67") (name "unconnected-(U$1-PA12-Pad33)") (class "Default")
      (node (ref "U$1") (pin "33") (pinfunction "PA12_33") (pintype "bidirectional"))
    )
    (net (code "68") (name "unconnected-(U$1-PA15-Pad38)") (class "Default")
      (node (ref "U$1") (pin "38") (pinfunction "PA15_38") (pintype "bidirectional"))
    )
    (net (code "69") (name "unconnected-(U$1-PB1-Pad19)") (class "Default")
      (node (ref "U$1") (pin "19") (pinfunction "PB1_19") (pintype "bidirectional"))
    )
    (net (code "70") (name "unconnected-(U$1-PB3-Pad39)") (class "Default")
      (node (ref "U$1") (pin "39") (pinfunction "PB3_39") (pintype "bidirectional"))
    )
    (net (code "71") (name "unconnected-(U$1-PB4-Pad40)") (class "Default")
      (node (ref "U$1") (pin "40") (pinfunction "PB4_40") (pintype "bidirectional"))
    )
    (net (code "72") (name "unconnected-(U$1-PB5-Pad41)") (class "Default")
      (node (ref "U$1") (pin "41") (pinfunction "PB5_41") (pintype "bidirectional"))
    )
    (net (code "73") (name "unconnected-(U$1-PB6-Pad42)") (class "Default")
      (node (ref "U$1") (pin "42") (pinfunction "PB6_42") (pintype "bidirectional"))
    )
    (net (code "74") (name "unconnected-(U$1-PB7-Pad43)") (class "Default")
      (node (ref "U$1") (pin "43") (pinfunction "PB7_43") (pintype "bidirectional"))
    )
    (net (code "75") (name "unconnected-(U$1-PB8-Pad45)") (class "Default")
      (node (ref "U$1") (pin "45") (pinfunction "PB8_45") (pintype "bidirectional"))
    )
    (net (code "76") (name "unconnected-(U$1-PB9-Pad46)") (class "Default")
      (node (ref "U$1") (pin "46") (pinfunction "PB9_46") (pintype "bidirectional"))
    )
    (net (code "77") (name "unconnected-(U$1-PB10-Pad21)") (class "Default")
      (node (ref "U$1") (pin "21") (pinfunction "PB10_21") (pintype "bidirectional"))
    )
    (net (code "78") (name "unconnected-(U$1-PB11-Pad22)") (class "Default")
      (node (ref "U$1") (pin "22") (pinfunction "PB11_22") (pintype "bidirectional"))
    )
    (net (code "79") (name "unconnected-(U$1-PB12-Pad25)") (class "Default")
      (node (ref "U$1") (pin "25") (pinfunction "PB12_25") (pintype "bidirectional"))
    )
    (net (code "80") (name "unconnected-(U$1-PB13-Pad26)") (class "Default")
      (node (ref "U$1") (pin "26") (pinfunction "PB13_26") (pintype "bidirectional"))
    )
    (net (code "81") (name "unconnected-(U$1-PB14-Pad27)") (class "Default")
      (node (ref "U$1") (pin "27") (pinfunction "PB14_27") (pintype "bidirectional"))
    )
    (net (code "82") (name "unconnected-(U$1-PB15-Pad28)") (class "Default")
      (node (ref "U$1") (pin "28") (pinfunction "PB15_28") (pintype "bidirectional"))
    )
    (net (code "83") (name "unconnected-(U$1-PC13_WKUP2-Pad2)") (class "Default")
      (node (ref "U$1") (pin "2") (pinfunction "PC13_WKUP2_2") (pintype "bidirectional"))
    )
    (net (code "84") (name "unconnected-(U$1-V_LCD-Pad1)") (class "Default")
      (node (ref "U$1") (pin "1") (pinfunction "V_LCD_1") (pintype "bidirectional"))
    )
    (net (code "85") (name "unconnected-(U$5-D2-Pad15)") (class "Default")
      (node (ref "U$5") (pin "15") (pinfunction "D2_15") (pintype "bidirectional"))
    )
    (net (code "86") (name "unconnected-(U$5-IN2-Pad16)") (class "Default")
      (node (ref "U$5") (pin "16") (pinfunction "IN2_16") (pintype "bidirectional"))
    )
    (net (code "87") (name "unconnected-(U$5-S2-Pad14)") (class "Default")
      (node (ref "U$5") (pin "14") (pinfunction "S2_14") (pintype "bidirectional"))
    )
    (net (code "88") (name "unconnected-(X2-Pad4)") (class "Default")
      (node (ref "X2") (pin "4") (pinfunction "4_4") (pintype "passive"))
    )
  )
)
